# InstrumentalAmplifier_in.net
KiCad netlist of a schematic drawn in Altium Designer
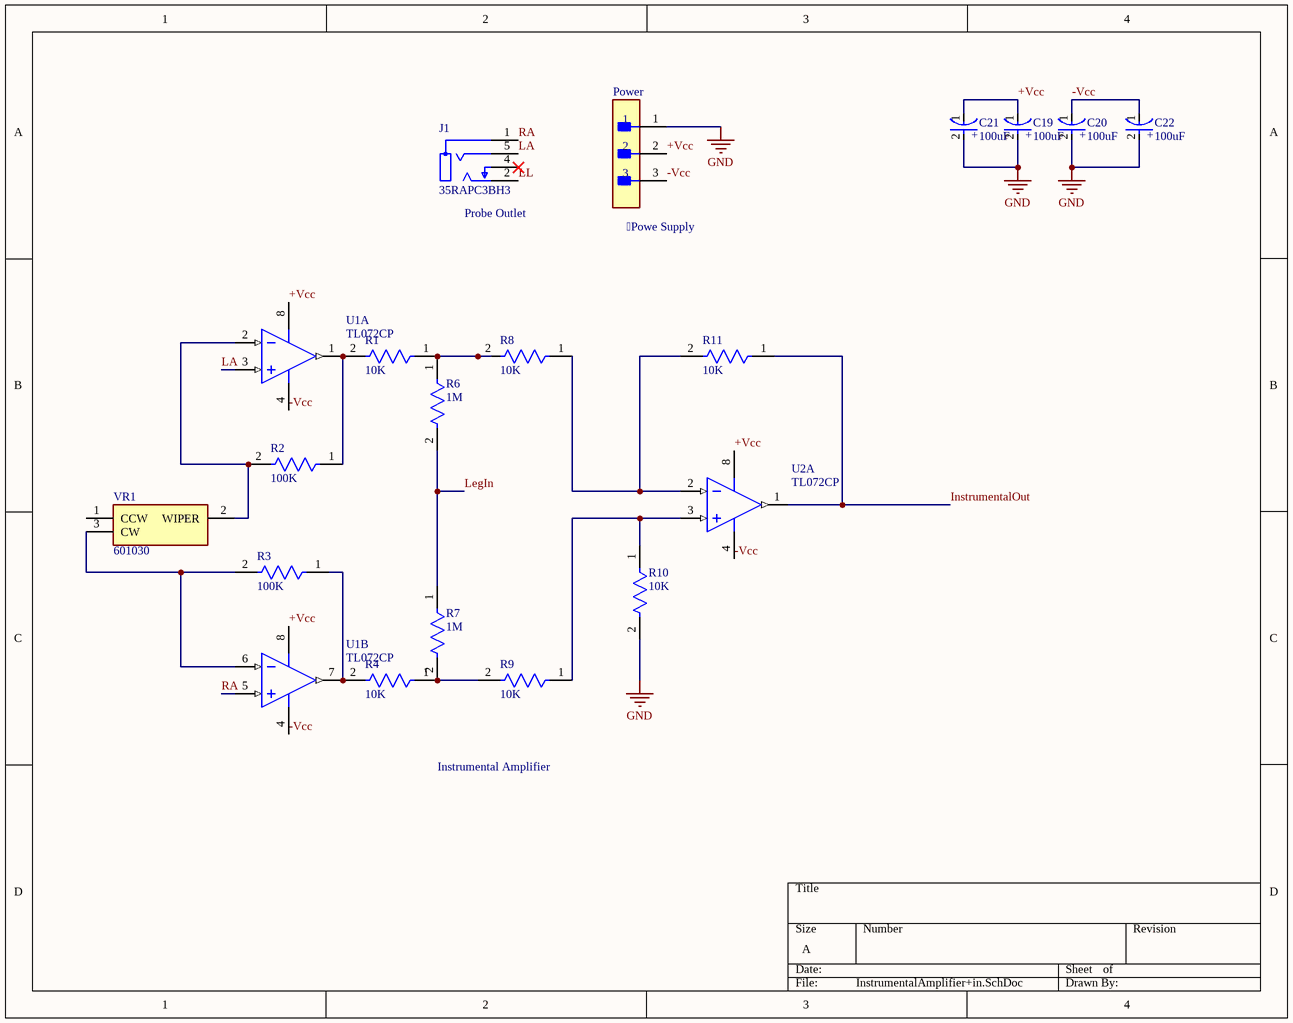
[diagram p0: InstrumentalAmplifier+in.SchDoc]

(export (version "E")
  (design (tool "Eeschema 10.0.6"))
  (components
    (comp (ref "C19")
      (value "100uF")
      (footprint "FP-RAD-TH-D_6_3_0_5-L_11-MFG")
      (description "Aluminum Electrolytic Capacitors (Radial Lead Type) 4.7uF ±20% 160V")
      (fields (field (name "VOLTAGE") "160V") (field (name "TOLERANCE") "20%"))
      (libsource (lib "Altium Content Vault") (part "203bc49f2ac43e59fd269a8c329ed05"))
    )
    (comp (ref "C20")
      (value "100uF")
      (footprint "FP-RAD-TH-D_6_3_0_5-L_11-MFG")
      (description "Aluminum Electrolytic Capacitors (Radial Lead Type) 4.7uF ±20% 160V")
      (fields (field (name "VOLTAGE") "160V") (field (name "TOLERANCE") "20%"))
      (libsource (lib "Altium Content Vault") (part "203bc49f2ac43e59fd269a8c329ed05"))
    )
    (comp (ref "C21")
      (value "100uF")
      (footprint "FP-RAD-TH-D_6_3_0_5-L_11-MFG")
      (description "Aluminum Electrolytic Capacitors (Radial Lead Type) 4.7uF ±20% 160V")
      (fields (field (name "VOLTAGE") "160V") (field (name "TOLERANCE") "20%"))
      (libsource (lib "Altium Content Vault") (part "203bc49f2ac43e59fd269a8c329ed05"))
    )
    (comp (ref "C22")
      (value "100uF")
      (footprint "FP-RAD-TH-D_6_3_0_5-L_11-MFG")
      (description "Aluminum Electrolytic Capacitors (Radial Lead Type) 4.7uF ±20% 160V")
      (fields (field (name "VOLTAGE") "160V") (field (name "TOLERANCE") "20%"))
      (libsource (lib "Altium Content Vault") (part "203bc49f2ac43e59fd269a8c329ed05"))
    )
    (comp (ref "J1")
      (value "35RAPC3BH3")
      (footprint "FP-35RAPC3BH3-MFG")
      (description "CONN JACK STEREO 3.5MM R/A")
      (libsource (lib "Altium Content Vault") (part "6593a1246df2d7246a2ad7da18ee256"))
    )
    (comp (ref "Power")
      (value "87224-3")
      (footprint "FP-87224-3-MFG")
      (description "CONN HEADER VERT 3POS 2.54MM")
      (libsource (lib "Altium Content Vault") (part "0d3f023dd272f625e17a2be33dea85f"))
    )
    (comp (ref "R1")
      (value "10K")
      (footprint "FP-CFR-25-MFG")
      (description "RES 10 OHM 1/4W 5% AXIAL")
      (fields (field (name "TOLERANCE") "5%"))
      (libsource (lib "Altium Content Vault") (part "1029c3af85768c4190bb7ad29bc67b5"))
    )
    (comp (ref "R2")
      (value "100K")
      (footprint "FP-CFR-25-MFG")
      (description "RES 10 OHM 1/4W 5% AXIAL")
      (fields (field (name "TOLERANCE") "5%"))
      (libsource (lib "Altium Content Vault") (part "1029c3af85768c4190bb7ad29bc67b5"))
    )
    (comp (ref "R3")
      (value "100K")
      (footprint "FP-CFR-25-MFG")
      (description "RES 10 OHM 1/4W 5% AXIAL")
      (fields (field (name "TOLERANCE") "5%"))
      (libsource (lib "Altium Content Vault") (part "1029c3af85768c4190bb7ad29bc67b5"))
    )
    (comp (ref "R4")
      (value "10K")
      (footprint "FP-CFR-25-MFG")
      (description "RES 10 OHM 1/4W 5% AXIAL")
      (fields (field (name "TOLERANCE") "5%"))
      (libsource (lib "Altium Content Vault") (part "1029c3af85768c4190bb7ad29bc67b5"))
    )
    (comp (ref "R6")
      (value "1M")
      (footprint "FP-CFR-25-MFG")
      (description "RES 10 OHM 1/4W 5% AXIAL")
      (fields (field (name "TOLERANCE") "5%"))
      (libsource (lib "Altium Content Vault") (part "1029c3af85768c4190bb7ad29bc67b5"))
    )
    (comp (ref "R7")
      (value "1M")
      (footprint "FP-CFR-25-MFG")
      (description "RES 10 OHM 1/4W 5% AXIAL")
      (fields (field (name "TOLERANCE") "5%"))
      (libsource (lib "Altium Content Vault") (part "1029c3af85768c4190bb7ad29bc67b5"))
    )
    (comp (ref "R8")
      (value "10K")
      (footprint "FP-CFR-25-MFG")
      (description "RES 10 OHM 1/4W 5% AXIAL")
      (fields (field (name "TOLERANCE") "5%"))
      (libsource (lib "Altium Content Vault") (part "1029c3af85768c4190bb7ad29bc67b5"))
    )
    (comp (ref "R9")
      (value "10K")
      (footprint "FP-CFR-25-MFG")
      (description "RES 10 OHM 1/4W 5% AXIAL")
      (fields (field (name "TOLERANCE") "5%"))
      (libsource (lib "Altium Content Vault") (part "1029c3af85768c4190bb7ad29bc67b5"))
    )
    (comp (ref "R10")
      (value "10K")
      (footprint "FP-CFR-25-MFG")
      (description "RES 10 OHM 1/4W 5% AXIAL")
      (fields (field (name "TOLERANCE") "5%"))
      (libsource (lib "Altium Content Vault") (part "1029c3af85768c4190bb7ad29bc67b5"))
    )
    (comp (ref "R11")
      (value "10K")
      (footprint "FP-CFR-25-MFG")
      (description "RES 10 OHM 1/4W 5% AXIAL")
      (fields (field (name "TOLERANCE") "5%"))
      (libsource (lib "Altium Content Vault") (part "1029c3af85768c4190bb7ad29bc67b5"))
    )
    (comp (ref "U1")
      (value "TL072CP")
      (footprint "P0008A")
      (fields (field (name "MANUFACTURER") "Texas Instruments"))
      (libsource (lib "Altium Content Vault") (part "TI-AMP-D6-2-8_D"))
    )
    (comp (ref "U2")
      (value "TL072CP")
      (footprint "P0008A")
      (fields (field (name "MANUFACTURER") "Texas Instruments"))
      (libsource (lib "Altium Content Vault") (part "TI-AMP-D6-2-8_D"))
    )
    (comp (ref "VR1")
      (value "601030")
      (footprint "SamacSys:601030")
      (description "Variable Resistor")
      (fields (field (name "MOUSER PART NUMBER") "581-601030"))
      (libsource (lib "*") (part "601030"))
    )
  )
  (nets
    (net (code "1") (name "/+Vcc") (class "Default")
      (node (ref "C19") (pin "1") (pinfunction "C_1") (pintype "passive"))
      (node (ref "C21") (pin "1") (pinfunction "C_1") (pintype "passive"))
      (node (ref "Power") (pin "2") (pinfunction "2_2") (pintype "passive"))
      (node (ref "U1") (pin "8") (pinfunction "VCC+_8") (pintype "power_in"))
      (node (ref "U2") (pin "8") (pinfunction "VCC+_8") (pintype "power_in"))
    )
    (net (code "2") (name "/-Vcc") (class "Default")
      (node (ref "C20") (pin "1") (pinfunction "C_1") (pintype "passive"))
      (node (ref "C22") (pin "1") (pinfunction "C_1") (pintype "passive"))
      (node (ref "Power") (pin "3") (pinfunction "3_3") (pintype "passive"))
      (node (ref "U1") (pin "4") (pinfunction "VCC-_4") (pintype "power_in"))
      (node (ref "U2") (pin "4") (pinfunction "VCC-_4") (pintype "power_in"))
    )
    (net (code "3") (name "/InstrumentalOut") (class "Default")
      (node (ref "R11") (pin "1") (pinfunction "1_1") (pintype "passive"))
      (node (ref "U2") (pin "1") (pinfunction "OUT1_1") (pintype "output"))
    )
    (net (code "4") (name "/LA") (class "Default")
      (node (ref "J1") (pin "5") (pinfunction "5_5") (pintype "passive"))
      (node (ref "U1") (pin "3") (pinfunction "IN1+_3") (pintype "input"))
    )
    (net (code "5") (name "/LL") (class "Default")
      (node (ref "J1") (pin "2") (pinfunction "2_2") (pintype "passive"))
    )
    (net (code "6") (name "/LegIn") (class "Default")
      (node (ref "R6") (pin "2") (pinfunction "2_2") (pintype "passive"))
      (node (ref "R7") (pin "1") (pinfunction "1_1") (pintype "passive"))
    )
    (net (code "7") (name "/RA") (class "Default")
      (node (ref "J1") (pin "1") (pinfunction "1_1") (pintype "passive"))
      (node (ref "U1") (pin "5") (pinfunction "IN2+_5") (pintype "input"))
    )
    (net (code "8") (name "GND") (class "Default")
      (node (ref "C19") (pin "2") (pinfunction "A_2") (pintype "passive"))
      (node (ref "C20") (pin "2") (pinfunction "A_2") (pintype "passive"))
      (node (ref "C21") (pin "2") (pinfunction "A_2") (pintype "passive"))
      (node (ref "C22") (pin "2") (pinfunction "A_2") (pintype "passive"))
      (node (ref "Power") (pin "1") (pinfunction "1_1") (pintype "passive"))
      (node (ref "R10") (pin "2") (pinfunction "2_2") (pintype "passive"))
    )
    (net (code "9") (name "Net-(R1-Pad1)") (class "Default")
      (node (ref "R1") (pin "1") (pinfunction "1_1") (pintype "passive"))
      (node (ref "R6") (pin "1") (pinfunction "1_1") (pintype "passive"))
      (node (ref "R8") (pin "2") (pinfunction "2_2") (pintype "passive"))
    )
    (net (code "10") (name "Net-(R4-Pad1)") (class "Default")
      (node (ref "R4") (pin "1") (pinfunction "1_1") (pintype "passive"))
      (node (ref "R7") (pin "2") (pinfunction "2_2") (pintype "passive"))
      (node (ref "R9") (pin "2") (pinfunction "2_2") (pintype "passive"))
    )
    (net (code "11") (name "Net-(U1A-IN1-)") (class "Default")
      (node (ref "R2") (pin "2") (pinfunction "2_2") (pintype "passive"))
      (node (ref "U1") (pin "2") (pinfunction "IN1-_2") (pintype "input"))
      (node (ref "VR1") (pin "2") (pinfunction "WIPER_2") (pintype "passive"))
    )
    (net (code "12") (name "Net-(U1A-OUT1)") (class "Default")
      (node (ref "R1") (pin "2") (pinfunction "2_2") (pintype "passive"))
      (node (ref "R2") (pin "1") (pinfunction "1_1") (pintype "passive"))
      (node (ref "U1") (pin "1") (pinfunction "OUT1_1") (pintype "output"))
    )
    (net (code "13") (name "Net-(U1B-IN2-)") (class "Default")
      (node (ref "R3") (pin "2") (pinfunction "2_2") (pintype "passive"))
      (node (ref "U1") (pin "6") (pinfunction "IN2-_6") (pintype "input"))
      (node (ref "VR1") (pin "3") (pinfunction "CW_3") (pintype "passive"))
    )
    (net (code "14") (name "Net-(U1B-OUT2)") (class "Default")
      (node (ref "R3") (pin "1") (pinfunction "1_1") (pintype "passive"))
      (node (ref "R4") (pin "2") (pinfunction "2_2") (pintype "passive"))
      (node (ref "U1") (pin "7") (pinfunction "OUT2_7") (pintype "output"))
    )
    (net (code "15") (name "Net-(U2A-IN1+)") (class "Default")
      (node (ref "R10") (pin "1") (pinfunction "1_1") (pintype "passive"))
      (node (ref "R9") (pin "1") (pinfunction "1_1") (pintype "passive"))
      (node (ref "U2") (pin "3") (pinfunction "IN1+_3") (pintype "input"))
    )
    (net (code "16") (name "Net-(U2A-IN1-)") (class "Default")
      (node (ref "R11") (pin "2") (pinfunction "2_2") (pintype "passive"))
      (node (ref "R8") (pin "1") (pinfunction "1_1") (pintype "passive"))
      (node (ref "U2") (pin "2") (pinfunction "IN1-_2") (pintype "input"))
    )
    (net (code "17") (name "unconnected-(J1-Pad4)") (class "Default")
      (node (ref "J1") (pin "4") (pinfunction "4_4") (pintype "passive+no_connect"))
    )
    (net (code "18") (name "unconnected-(VR1-CCW-Pad1)") (class "Default")
      (node (ref "VR1") (pin "1") (pinfunction "CCW_1") (pintype "passive"))
    )
  )
)
